# SYSTEM.net
KiCad netlist of a schematic drawn in Altium Designer
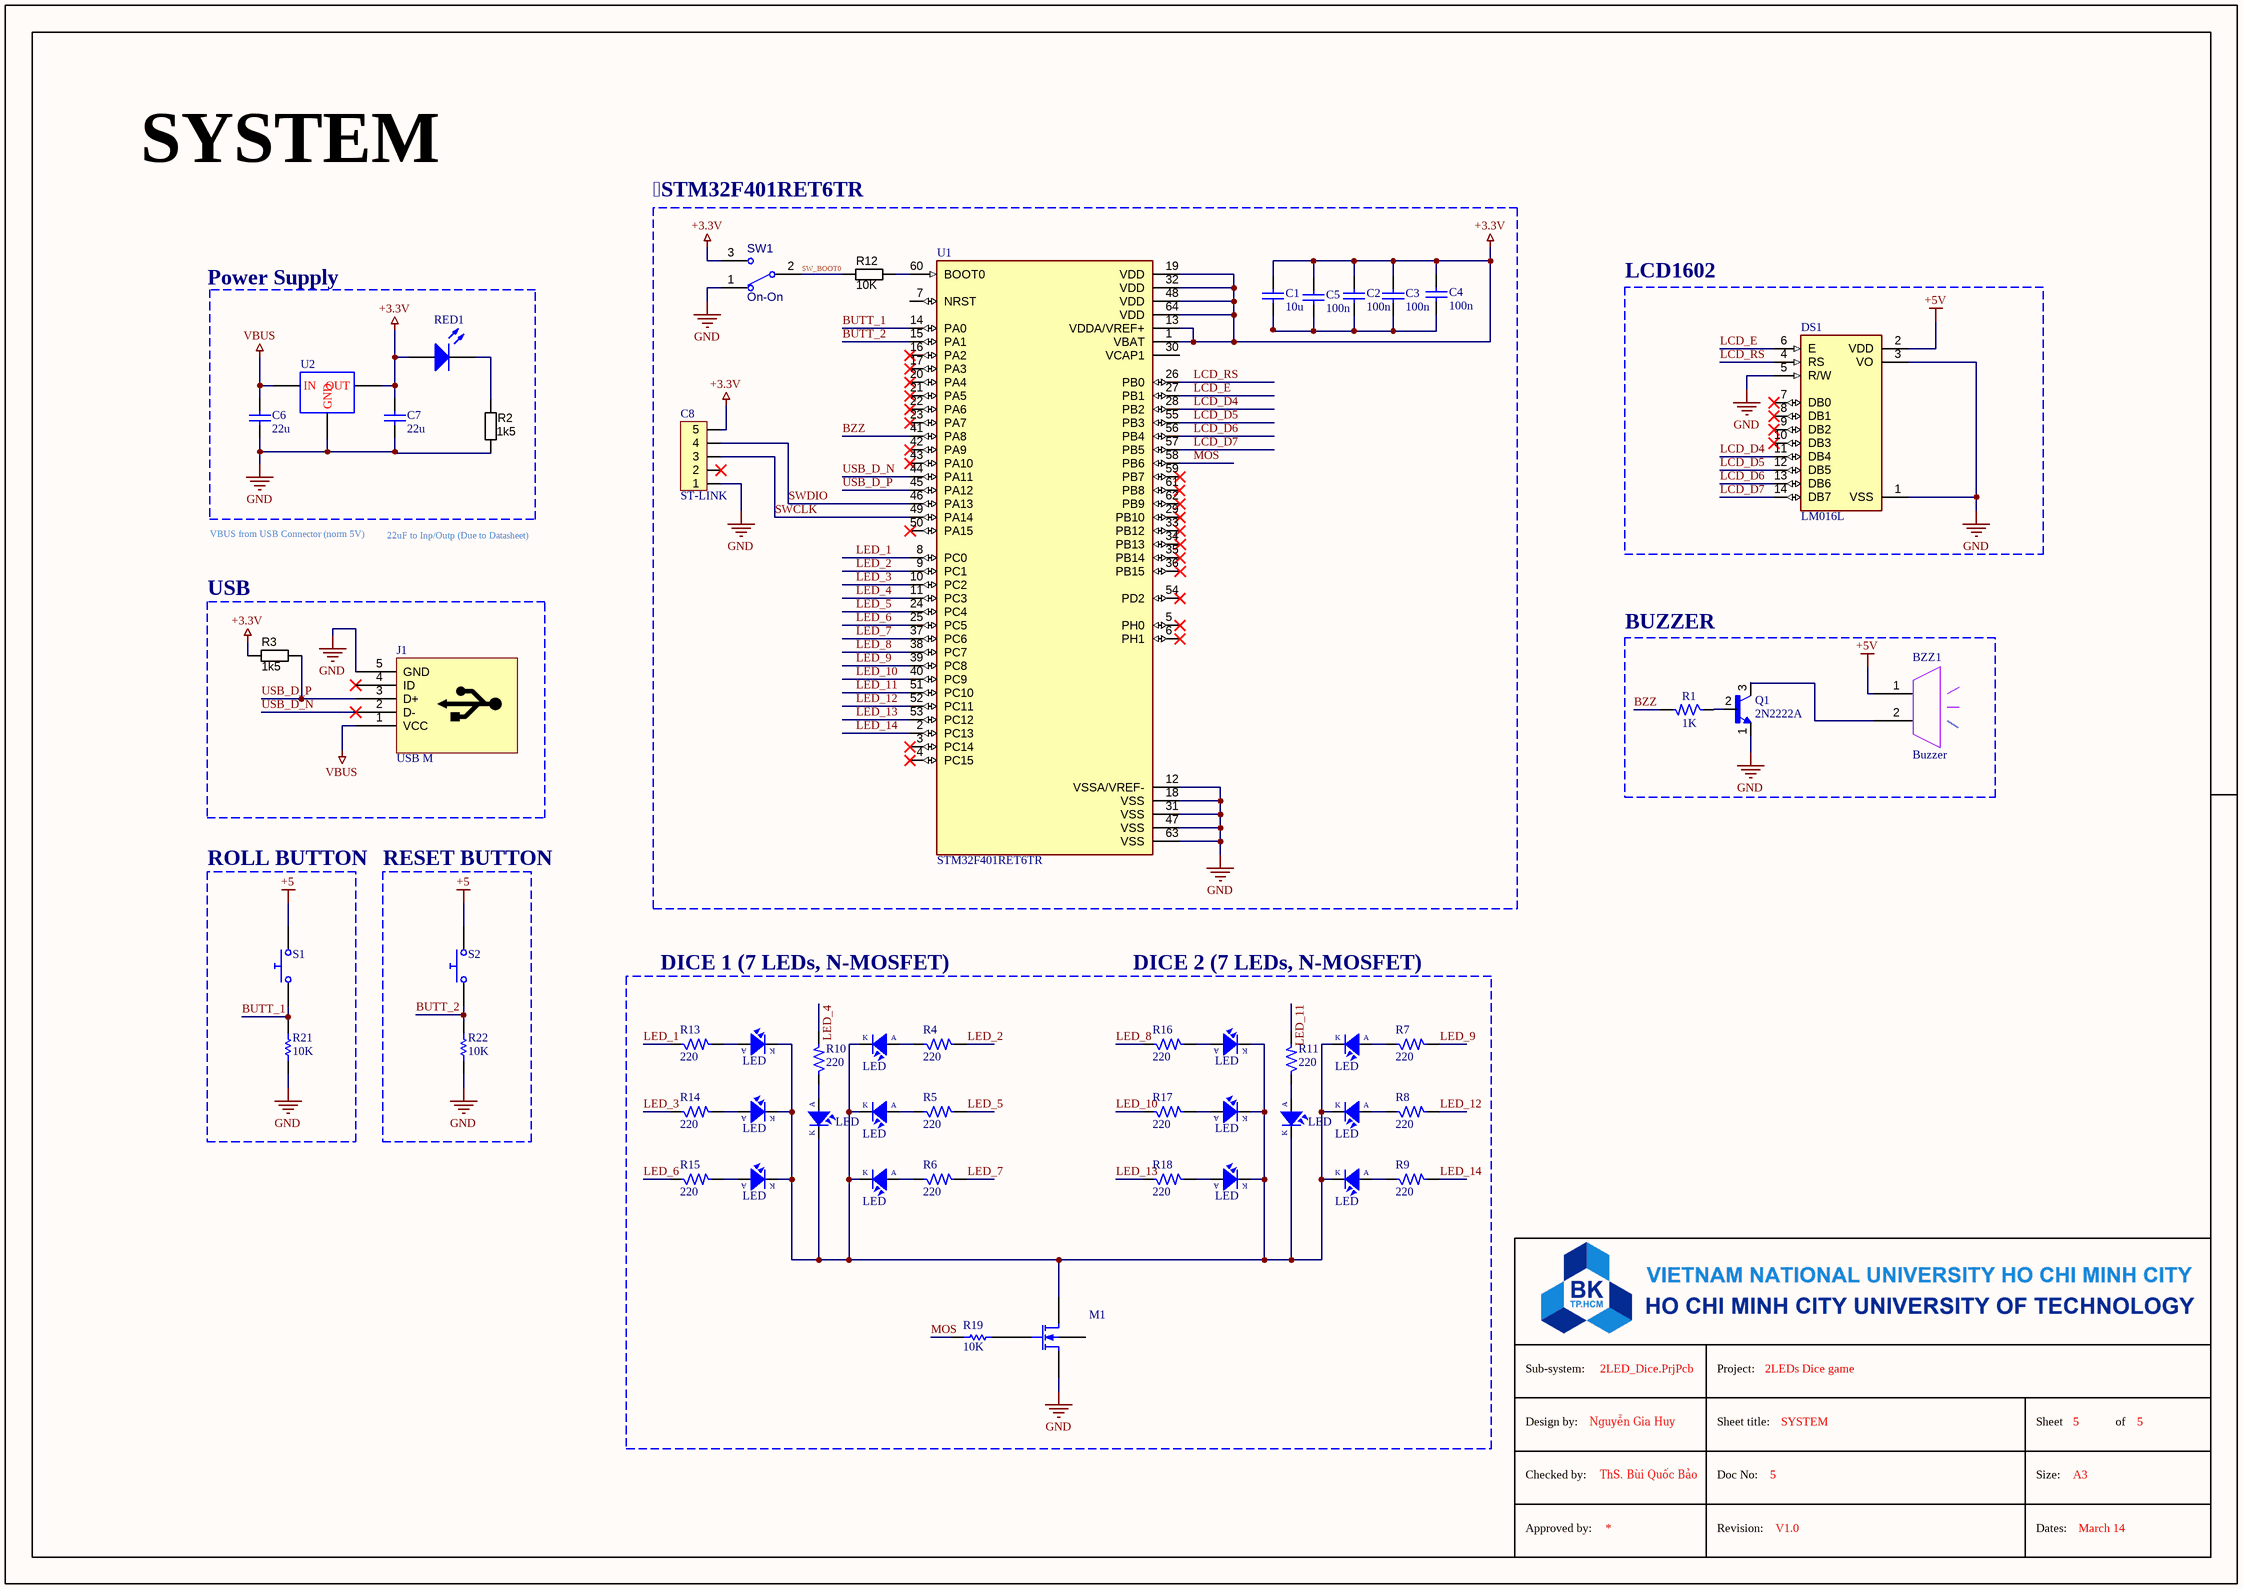
[diagram p0: SYSTEM.SchDoc]

(export (version "E")
  (design (tool "Eeschema 10.0.6"))
  (components
    (comp (ref "BZZ1")
      (value "Buzzer")
      (footprint "buzzer 5V")
      (libsource (lib "my Library") (part "Buzzer"))
    )
    (comp (ref "C1")
      (value "10u")
      (footprint "tu 0402")
      (description "Capacitor")
      (libsource (lib "Simulation Generic Components") (part "Capacitor"))
    )
    (comp (ref "C2")
      (value "100n")
      (footprint "tu 0402")
      (description "Capacitor")
      (libsource (lib "Simulation Generic Components") (part "Capacitor"))
    )
    (comp (ref "C3")
      (value "100n")
      (footprint "tu 0402")
      (description "Capacitor")
      (libsource (lib "Simulation Generic Components") (part "Capacitor"))
    )
    (comp (ref "C4")
      (value "100n")
      (footprint "tu 0402")
      (description "Capacitor")
      (libsource (lib "Simulation Generic Components") (part "Capacitor"))
    )
    (comp (ref "C5")
      (value "100n")
      (footprint "tu 0402")
      (description "Capacitor")
      (libsource (lib "Simulation Generic Components") (part "Capacitor"))
    )
    (comp (ref "C6")
      (value "22u")
      (footprint "CAPC2012X94N")
      (description "Capacitor")
      (libsource (lib "Simulation Generic Components") (part "Capacitor"))
    )
    (comp (ref "C7")
      (value "22u")
      (footprint "CAPC2012X94N")
      (description "Capacitor")
      (libsource (lib "Simulation Generic Components") (part "Capacitor"))
    )
    (comp (ref "C8")
      (value "ST-LINK")
      (footprint "HDR5")
      (description "Header IDC, 5 x 1 Pin Vertical 2.54mm Pitch (Non-Boxed, Male)")
      (fields
        (field (name "MANUFACTURER") "Würth Elektronik eiSos GmbH")
        (field (name "PARTNO") "613002143121")
        (field (name "CREATED BY") "Karrer Zheng")
      )
      (libsource (lib "LIBRARY") (part "Header5"))
    )
    (comp (ref "DS1")
      (value "LM016L")
      (footprint "MODULE_LCD-16X2")
      (description "Display Lcd 35x75mm")
      (fields (field (name "MF") "Hitachi"))
      (libsource (lib "LM016L") (part "LM016L"))
    )
    (comp (ref "J1")
      (value "USB M")
      (footprint "USB-Micr-B-FCI-SMD")
      (libsource (lib "my Library") (part "USB M"))
    )
    (comp (ref "LED1")
      (value "LED")
      (footprint "LED-3")
      (description "LED Single colour Green and Red")
      (libsource (lib "my Library") (part "LED"))
    )
    (comp (ref "LED2")
      (value "LED")
      (footprint "LED-3")
      (description "LED Single colour Green and Red")
      (libsource (lib "my Library") (part "LED"))
    )
    (comp (ref "LED3")
      (value "LED")
      (footprint "LED-3")
      (description "LED Single colour Green and Red")
      (libsource (lib "my Library") (part "LED"))
    )
    (comp (ref "LED4")
      (value "LED")
      (footprint "LED-3")
      (description "LED Single colour Green and Red")
      (libsource (lib "my Library") (part "LED"))
    )
    (comp (ref "LED5")
      (value "LED")
      (footprint "LED-3")
      (description "LED Single colour Green and Red")
      (libsource (lib "my Library") (part "LED"))
    )
    (comp (ref "LED6")
      (value "LED")
      (footprint "LED-3")
      (description "LED Single colour Green and Red")
      (libsource (lib "my Library") (part "LED"))
    )
    (comp (ref "LED7")
      (value "LED")
      (footprint "LED-3")
      (description "LED Single colour Green and Red")
      (libsource (lib "my Library") (part "LED"))
    )
    (comp (ref "LED8")
      (value "LED")
      (footprint "LED-3")
      (description "LED Single colour Green and Red")
      (libsource (lib "my Library") (part "LED"))
    )
    (comp (ref "LED9")
      (value "LED")
      (footprint "LED-3")
      (description "LED Single colour Green and Red")
      (libsource (lib "my Library") (part "LED"))
    )
    (comp (ref "LED10")
      (value "LED")
      (footprint "LED-3")
      (description "LED Single colour Green and Red")
      (libsource (lib "my Library") (part "LED"))
    )
    (comp (ref "LED11")
      (value "LED")
      (footprint "LED-3")
      (description "LED Single colour Green and Red")
      (libsource (lib "my Library") (part "LED"))
    )
    (comp (ref "LED12")
      (value "LED")
      (footprint "LED-3")
      (description "LED Single colour Green and Red")
      (libsource (lib "my Library") (part "LED"))
    )
    (comp (ref "LED13")
      (value "LED")
      (footprint "LED-3")
      (description "LED Single colour Green and Red")
      (libsource (lib "my Library") (part "LED"))
    )
    (comp (ref "LED14")
      (value "LED")
      (footprint "LED-3")
      (description "LED Single colour Green and Red")
      (libsource (lib "my Library") (part "LED"))
    )
    (comp (ref "M1")
      (value "N-channel MOS1 MOSFET Shichman and Hodges Model")
      (footprint "TO254P1054X469X1930-3")
      (libsource (lib "Simulation Generic Components") (part "MOSFET N-ch Lev1"))
    )
    (comp (ref "Q1")
      (value "2N2222A")
      (footprint "TO127P584H533-3")
      (description "Bipolar (BJT) Transistor NPN 50 V 800 mA - 500 mW Surface Mount 4-SMD")
      (fields (field (name "MF") "Microsemi Corporation"))
      (libsource (lib "2N2222A") (part "2N2222A"))
    )
    (comp (ref "R1")
      (value "1K")
      (footprint "RES-SMD-0402")
      (description "Res")
      (libsource (lib "my Library") (part "Res"))
    )
    (comp (ref "R2")
      (value "1k5")
      (footprint "RES-SMD-0402")
      (description "Resistor SMD chip 1k Ohm 0.063W 5% 0402")
      (fields (field (name "TOLERANCE") "±5%") (field (name "Comment") "Thick Film"))
      (libsource (lib "my Library") (part "RES_0402"))
    )
    (comp (ref "R3")
      (value "1k5")
      (footprint "RES-SMD-0402")
      (description "Resistor SMD chip 1k Ohm 0.063W 5% 0402")
      (fields (field (name "TOLERANCE") "±5%") (field (name "Comment") "Thick Film"))
      (libsource (lib "my Library") (part "RES_0402"))
    )
    (comp (ref "R4")
      (value "220")
      (footprint "RES-SMD-0402")
      (description "Res")
      (libsource (lib "my Library") (part "Res"))
    )
    (comp (ref "R5")
      (value "220")
      (footprint "RES-SMD-0402")
      (description "Res")
      (libsource (lib "my Library") (part "Res"))
    )
    (comp (ref "R6")
      (value "220")
      (footprint "RES-SMD-0402")
      (description "Res")
      (libsource (lib "my Library") (part "Res"))
    )
    (comp (ref "R7")
      (value "220")
      (footprint "RES-SMD-0402")
      (description "Res")
      (libsource (lib "my Library") (part "Res"))
    )
    (comp (ref "R8")
      (value "220")
      (footprint "RES-SMD-0402")
      (description "Res")
      (libsource (lib "my Library") (part "Res"))
    )
    (comp (ref "R9")
      (value "220")
      (footprint "RES-SMD-0402")
      (description "Res")
      (libsource (lib "my Library") (part "Res"))
    )
    (comp (ref "R10")
      (value "220")
      (footprint "RES-SMD-0402")
      (description "Res")
      (libsource (lib "my Library") (part "Res"))
    )
    (comp (ref "R11")
      (value "220")
      (footprint "RES-SMD-0402")
      (description "Res")
      (libsource (lib "my Library") (part "Res"))
    )
    (comp (ref "R12")
      (value "10K")
      (footprint "RES-SMD-0402")
      (description "Resistor SMD chip 1k Ohm 0.063W 5% 0402")
      (fields (field (name "TOLERANCE") "±5%") (field (name "Comment") "Thick Film"))
      (libsource (lib "") (part "RES_0402_1"))
    )
    (comp (ref "R13")
      (value "220")
      (footprint "RES-SMD-0402")
      (description "Res")
      (libsource (lib "my Library") (part "Res"))
    )
    (comp (ref "R14")
      (value "220")
      (footprint "RES-SMD-0402")
      (description "Res")
      (libsource (lib "my Library") (part "Res"))
    )
    (comp (ref "R15")
      (value "220")
      (footprint "RES-SMD-0402")
      (description "Res")
      (libsource (lib "my Library") (part "Res"))
    )
    (comp (ref "R16")
      (value "220")
      (footprint "RES-SMD-0402")
      (description "Res")
      (libsource (lib "my Library") (part "Res"))
    )
    (comp (ref "R17")
      (value "220")
      (footprint "RES-SMD-0402")
      (description "Res")
      (libsource (lib "my Library") (part "Res"))
    )
    (comp (ref "R18")
      (value "220")
      (footprint "RES-SMD-0402")
      (description "Res")
      (libsource (lib "my Library") (part "Res"))
    )
    (comp (ref "R19")
      (value "10K")
      (footprint "RES-SMD-0402")
      (description "Resistor")
      (libsource (lib "Simulation Generic Components") (part "Resistor"))
    )
    (comp (ref "R21")
      (value "10K")
      (footprint "RES-SMD-0402")
      (description "Resistor")
      (libsource (lib "Simulation Generic Components") (part "Resistor"))
    )
    (comp (ref "R22")
      (value "10K")
      (footprint "RES-SMD-0402")
      (description "Resistor")
      (libsource (lib "Simulation Generic Components") (part "Resistor"))
    )
    (comp (ref "RED1")
      (value "Light-Emitting Diode")
      (footprint "LED-RED-0805")
      (libsource (lib "Simulation Generic Components") (part "LED"))
    )
    (comp (ref "S1")
      (value "Push Button Normally Opened")
      (footprint "SW4_SMD")
      (libsource (lib "Simulation Generic Components") (part "Push Button NO"))
    )
    (comp (ref "S2")
      (value "Push Button Normally Opened")
      (footprint "SW4_SMD")
      (libsource (lib "Simulation Generic Components") (part "Push Button NO"))
    )
    (comp (ref "SW1")
      (value "ON-ON")
      (footprint "SW4_SMD")
      (description "Switch THD vertical toggle SPDT")
      (fields (field (name "SWITCH FUNCTION") "On-On"))
      (libsource (lib "my Library") (part "SW_THD_SPDT_On-On"))
    )
    (comp (ref "U1")
      (value "STM32F401RET6TR")
      (footprint "QFP50P1200X1200X160-64N")
      (fields (field (name "MF") "STMicroelectronics"))
      (libsource (lib "STM32F401RET6TR") (part "STM32F401RET6TR"))
    )
    (comp (ref "U2")
      (value "Positive Fixed Voltage regulator")
      (footprint "AMS1117_3v3")
      (libsource (lib "Simulation Generic Components") (part "Linear Voltage Regulator (Fixed)"))
    )
  )
  (nets
    (net (code "1") (name "+3.3V") (class "Default")
      (node (ref "C1") (pin "1") (pinfunction "1_1") (pintype "passive"))
      (node (ref "C2") (pin "1") (pinfunction "1_1") (pintype "passive"))
      (node (ref "C3") (pin "1") (pinfunction "1_1") (pintype "passive"))
      (node (ref "C4") (pin "1") (pinfunction "1_1") (pintype "passive"))
      (node (ref "C5") (pin "1") (pinfunction "1_1") (pintype "passive"))
      (node (ref "C7") (pin "1") (pinfunction "1_1") (pintype "passive"))
      (node (ref "C8") (pin "5") (pinfunction "5_5") (pintype "passive"))
      (node (ref "R3") (pin "1") (pinfunction "1_1") (pintype "passive"))
      (node (ref "RED1") (pin "1") (pinfunction "A_1") (pintype "passive"))
      (node (ref "SW1") (pin "3") (pinfunction "3_3") (pintype "passive"))
      (node (ref "U1") (pin "1") (pinfunction "VBAT_1") (pintype "power_in"))
      (node (ref "U1") (pin "13") (pinfunction "VDDA/VREF+_13") (pintype "power_in"))
      (node (ref "U1") (pin "19") (pinfunction "VDD_19") (pintype "power_in"))
      (node (ref "U1") (pin "32") (pinfunction "VDD_32") (pintype "power_in"))
      (node (ref "U1") (pin "48") (pinfunction "VDD_48") (pintype "power_in"))
      (node (ref "U1") (pin "64") (pinfunction "VDD_64") (pintype "power_in"))
      (node (ref "U2") (pin "3") (pinfunction "OUT_3") (pintype "passive"))
    )
    (net (code "2") (name "+5") (class "Default")
      (node (ref "S1") (pin "2") (pinfunction "2_2") (pintype "passive"))
      (node (ref "S2") (pin "2") (pinfunction "2_2") (pintype "passive"))
    )
    (net (code "3") (name "+5V") (class "Default")
      (node (ref "BZZ1") (pin "1") (pinfunction "1_1") (pintype "passive"))
      (node (ref "DS1") (pin "2") (pinfunction "VDD_2") (pintype "power_in"))
    )
    (net (code "4") (name "/BUTT_1") (class "Default")
      (node (ref "R21") (pin "2") (pinfunction "2_2") (pintype "passive"))
      (node (ref "S1") (pin "1") (pinfunction "1_1") (pintype "passive"))
      (node (ref "U1") (pin "14") (pinfunction "PA0_14") (pintype "bidirectional"))
    )
    (net (code "5") (name "/BUTT_2") (class "Default")
      (node (ref "R22") (pin "2") (pinfunction "2_2") (pintype "passive"))
      (node (ref "S2") (pin "1") (pinfunction "1_1") (pintype "passive"))
      (node (ref "U1") (pin "15") (pinfunction "PA1_15") (pintype "bidirectional"))
    )
    (net (code "6") (name "/BZZ") (class "Default")
      (node (ref "R1") (pin "2") (pinfunction "2_2") (pintype "passive"))
      (node (ref "U1") (pin "41") (pinfunction "PA8_41") (pintype "bidirectional"))
    )
    (net (code "7") (name "/LCD_D4") (class "Default")
      (node (ref "DS1") (pin "11") (pinfunction "DB4_11") (pintype "bidirectional"))
      (node (ref "U1") (pin "28") (pinfunction "PB2_28") (pintype "bidirectional"))
    )
    (net (code "8") (name "/LCD_D5") (class "Default")
      (node (ref "DS1") (pin "12") (pinfunction "DB5_12") (pintype "bidirectional"))
      (node (ref "U1") (pin "55") (pinfunction "PB3_55") (pintype "bidirectional"))
    )
    (net (code "9") (name "/LCD_D6") (class "Default")
      (node (ref "DS1") (pin "13") (pinfunction "DB6_13") (pintype "bidirectional"))
      (node (ref "U1") (pin "56") (pinfunction "PB4_56") (pintype "bidirectional"))
    )
    (net (code "10") (name "/LCD_D7") (class "Default")
      (node (ref "DS1") (pin "14") (pinfunction "DB7_14") (pintype "bidirectional"))
      (node (ref "U1") (pin "57") (pinfunction "PB5_57") (pintype "bidirectional"))
    )
    (net (code "11") (name "/LCD_E") (class "Default")
      (node (ref "DS1") (pin "6") (pinfunction "E_6") (pintype "input"))
      (node (ref "U1") (pin "27") (pinfunction "PB1_27") (pintype "bidirectional"))
    )
    (net (code "12") (name "/LCD_RS") (class "Default")
      (node (ref "DS1") (pin "4") (pinfunction "RS_4") (pintype "input"))
      (node (ref "U1") (pin "26") (pinfunction "PB0_26") (pintype "bidirectional"))
    )
    (net (code "13") (name "/LED_1") (class "Default")
      (node (ref "R13") (pin "1") (pinfunction "1_1") (pintype "passive"))
      (node (ref "U1") (pin "8") (pinfunction "PC0_8") (pintype "bidirectional"))
    )
    (net (code "14") (name "/LED_2") (class "Default")
      (node (ref "R4") (pin "2") (pinfunction "2_2") (pintype "passive"))
      (node (ref "U1") (pin "9") (pinfunction "PC1_9") (pintype "bidirectional"))
    )
    (net (code "15") (name "/LED_3") (class "Default")
      (node (ref "R14") (pin "1") (pinfunction "1_1") (pintype "passive"))
      (node (ref "U1") (pin "10") (pinfunction "PC2_10") (pintype "bidirectional"))
    )
    (net (code "16") (name "/LED_4") (class "Default")
      (node (ref "R10") (pin "2") (pinfunction "2_2") (pintype "passive"))
      (node (ref "U1") (pin "11") (pinfunction "PC3_11") (pintype "bidirectional"))
    )
    (net (code "17") (name "/LED_5") (class "Default")
      (node (ref "R5") (pin "2") (pinfunction "2_2") (pintype "passive"))
      (node (ref "U1") (pin "24") (pinfunction "PC4_24") (pintype "bidirectional"))
    )
    (net (code "18") (name "/LED_6") (class "Default")
      (node (ref "R15") (pin "1") (pinfunction "1_1") (pintype "passive"))
      (node (ref "U1") (pin "25") (pinfunction "PC5_25") (pintype "bidirectional"))
    )
    (net (code "19") (name "/LED_7") (class "Default")
      (node (ref "R6") (pin "2") (pinfunction "2_2") (pintype "passive"))
      (node (ref "U1") (pin "37") (pinfunction "PC6_37") (pintype "bidirectional"))
    )
    (net (code "20") (name "/LED_8") (class "Default")
      (node (ref "R16") (pin "1") (pinfunction "1_1") (pintype "passive"))
      (node (ref "U1") (pin "38") (pinfunction "PC7_38") (pintype "bidirectional"))
    )
    (net (code "21") (name "/LED_9") (class "Default")
      (node (ref "R7") (pin "2") (pinfunction "2_2") (pintype "passive"))
      (node (ref "U1") (pin "39") (pinfunction "PC8_39") (pintype "bidirectional"))
    )
    (net (code "22") (name "/LED_10") (class "Default")
      (node (ref "R17") (pin "1") (pinfunction "1_1") (pintype "passive"))
      (node (ref "U1") (pin "40") (pinfunction "PC9_40") (pintype "bidirectional"))
    )
    (net (code "23") (name "/LED_11") (class "Default")
      (node (ref "R11") (pin "2") (pinfunction "2_2") (pintype "passive"))
      (node (ref "U1") (pin "51") (pinfunction "PC10_51") (pintype "bidirectional"))
    )
    (net (code "24") (name "/LED_12") (class "Default")
      (node (ref "R8") (pin "2") (pinfunction "2_2") (pintype "passive"))
      (node (ref "U1") (pin "52") (pinfunction "PC11_52") (pintype "bidirectional"))
    )
    (net (code "25") (name "/LED_13") (class "Default")
      (node (ref "R18") (pin "1") (pinfunction "1_1") (pintype "passive"))
      (node (ref "U1") (pin "53") (pinfunction "PC12_53") (pintype "bidirectional"))
    )
    (net (code "26") (name "/LED_14") (class "Default")
      (node (ref "R9") (pin "2") (pinfunction "2_2") (pintype "passive"))
      (node (ref "U1") (pin "2") (pinfunction "PC13_2") (pintype "bidirectional"))
    )
    (net (code "27") (name "/MOS") (class "Default")
      (node (ref "R19") (pin "2") (pinfunction "2_2") (pintype "passive"))
      (node (ref "U1") (pin "58") (pinfunction "PB6_58") (pintype "bidirectional"))
    )
    (net (code "28") (name "/SWCLK") (class "Default")
      (node (ref "C8") (pin "3") (pinfunction "3_3") (pintype "passive"))
      (node (ref "U1") (pin "49") (pinfunction "PA14_49") (pintype "bidirectional"))
    )
    (net (code "29") (name "/SWDIO") (class "Default")
      (node (ref "C8") (pin "4") (pinfunction "4_4") (pintype "passive"))
      (node (ref "U1") (pin "46") (pinfunction "PA13_46") (pintype "bidirectional"))
    )
    (net (code "30") (name "/SW_BOOT0") (class "Default")
      (node (ref "R12") (pin "2") (pinfunction "2_2") (pintype "passive"))
      (node (ref "SW1") (pin "2") (pinfunction "2_2") (pintype "passive"))
    )
    (net (code "31") (name "/USB_D_N") (class "Default")
      (node (ref "J1") (pin "2") (pinfunction "D-_2") (pintype "passive"))
      (node (ref "U1") (pin "44") (pinfunction "PA11_44") (pintype "bidirectional"))
    )
    (net (code "32") (name "/USB_D_P") (class "Default")
      (node (ref "J1") (pin "3") (pinfunction "D+_3") (pintype "passive"))
      (node (ref "R3") (pin "2") (pinfunction "2_2") (pintype "passive"))
      (node (ref "U1") (pin "45") (pinfunction "PA12_45") (pintype "bidirectional"))
    )
    (net (code "33") (name "GND") (class "Default")
      (node (ref "C6") (pin "2") (pinfunction "2_2") (pintype "passive"))
      (node (ref "C7") (pin "2") (pinfunction "2_2") (pintype "passive"))
      (node (ref "C8") (pin "1") (pinfunction "1_1") (pintype "passive"))
      (node (ref "DS1") (pin "1") (pinfunction "VSS_1") (pintype "power_in"))
      (node (ref "DS1") (pin "3") (pinfunction "VO_3") (pintype "power_in"))
      (node (ref "DS1") (pin "5") (pinfunction "R/W_5") (pintype "input"))
      (node (ref "J1") (pin "5") (pinfunction "GND_5") (pintype "passive"))
      (node (ref "M1") (pin "3") (pinfunction "S_3") (pintype "passive"))
      (node (ref "Q1") (pin "1") (pinfunction "E_1") (pintype "passive"))
      (node (ref "R2") (pin "1") (pinfunction "1_1") (pintype "passive"))
      (node (ref "R21") (pin "1") (pinfunction "1_1") (pintype "passive"))
      (node (ref "R22") (pin "1") (pinfunction "1_1") (pintype "passive"))
      (node (ref "SW1") (pin "1") (pinfunction "1_1") (pintype "passive"))
      (node (ref "U1") (pin "12") (pinfunction "VSSA/VREF-_12") (pintype "power_in"))
      (node (ref "U1") (pin "18") (pinfunction "VSS_18") (pintype "power_in"))
      (node (ref "U1") (pin "31") (pinfunction "VSS_31") (pintype "power_in"))
      (node (ref "U1") (pin "47") (pinfunction "VSS_47") (pintype "power_in"))
      (node (ref "U1") (pin "63") (pinfunction "VSS_63") (pintype "power_in"))
      (node (ref "U2") (pin "2") (pinfunction "GND_2") (pintype "passive"))
    )
    (net (code "34") (name "Net-(C1-Pad2)") (class "Default")
      (node (ref "C1") (pin "2") (pinfunction "2_2") (pintype "passive"))
      (node (ref "C2") (pin "2") (pinfunction "2_2") (pintype "passive"))
      (node (ref "C3") (pin "2") (pinfunction "2_2") (pintype "passive"))
      (node (ref "C4") (pin "2") (pinfunction "2_2") (pintype "passive"))
      (node (ref "C5") (pin "2") (pinfunction "2_2") (pintype "passive"))
    )
    (net (code "35") (name "Net-(LED1-A)") (class "Default")
      (node (ref "LED1") (pin "1") (pinfunction "A_1") (pintype "passive"))
      (node (ref "R4") (pin "1") (pinfunction "1_1") (pintype "passive"))
    )
    (net (code "36") (name "Net-(LED1-K)") (class "Default")
      (node (ref "LED1") (pin "2") (pinfunction "K_2") (pintype "passive"))
      (node (ref "LED10") (pin "2") (pinfunction "K_2") (pintype "passive"))
      (node (ref "LED11") (pin "2") (pinfunction "K_2") (pintype "passive"))
      (node (ref "LED12") (pin "2") (pinfunction "K_2") (pintype "passive"))
      (node (ref "LED13") (pin "2") (pinfunction "K_2") (pintype "passive"))
      (node (ref "LED14") (pin "2") (pinfunction "K_2") (pintype "passive"))
      (node (ref "LED2") (pin "2") (pinfunction "K_2") (pintype "passive"))
      (node (ref "LED3") (pin "2") (pinfunction "K_2") (pintype "passive"))
      (node (ref "LED4") (pin "2") (pinfunction "K_2") (pintype "passive"))
      (node (ref "LED5") (pin "2") (pinfunction "K_2") (pintype "passive"))
      (node (ref "LED6") (pin "2") (pinfunction "K_2") (pintype "passive"))
      (node (ref "LED7") (pin "2") (pinfunction "K_2") (pintype "passive"))
      (node (ref "LED8") (pin "2") (pinfunction "K_2") (pintype "passive"))
      (node (ref "LED9") (pin "2") (pinfunction "K_2") (pintype "passive"))
      (node (ref "M1") (pin "1") (pinfunction "D_1") (pintype "passive"))
    )
    (net (code "37") (name "Net-(LED2-A)") (class "Default")
      (node (ref "LED2") (pin "1") (pinfunction "A_1") (pintype "passive"))
      (node (ref "R5") (pin "1") (pinfunction "1_1") (pintype "passive"))
    )
    (net (code "38") (name "Net-(LED3-A)") (class "Default")
      (node (ref "LED3") (pin "1") (pinfunction "A_1") (pintype "passive"))
      (node (ref "R6") (pin "1") (pinfunction "1_1") (pintype "passive"))
    )
    (net (code "39") (name "Net-(LED4-A)") (class "Default")
      (node (ref "LED4") (pin "1") (pinfunction "A_1") (pintype "passive"))
      (node (ref "R7") (pin "1") (pinfunction "1_1") (pintype "passive"))
    )
    (net (code "40") (name "Net-(LED5-A)") (class "Default")
      (node (ref "LED5") (pin "1") (pinfunction "A_1") (pintype "passive"))
      (node (ref "R8") (pin "1") (pinfunction "1_1") (pintype "passive"))
    )
    (net (code "41") (name "Net-(LED6-A)") (class "Default")
      (node (ref "LED6") (pin "1") (pinfunction "A_1") (pintype "passive"))
      (node (ref "R9") (pin "1") (pinfunction "1_1") (pintype "passive"))
    )
    (net (code "42") (name "Net-(LED7-A)") (class "Default")
      (node (ref "LED7") (pin "1") (pinfunction "A_1") (pintype "passive"))
      (node (ref "R10") (pin "1") (pinfunction "1_1") (pintype "passive"))
    )
    (net (code "43") (name "Net-(LED8-A)") (class "Default")
      (node (ref "LED8") (pin "1") (pinfunction "A_1") (pintype "passive"))
      (node (ref "R11") (pin "1") (pinfunction "1_1") (pintype "passive"))
    )
    (net (code "44") (name "Net-(LED9-A)") (class "Default")
      (node (ref "LED9") (pin "1") (pinfunction "A_1") (pintype "passive"))
      (node (ref "R13") (pin "2") (pinfunction "2_2") (pintype "passive"))
    )
    (net (code "45") (name "Net-(LED10-A)") (class "Default")
      (node (ref "LED10") (pin "1") (pinfunction "A_1") (pintype "passive"))
      (node (ref "R14") (pin "2") (pinfunction "2_2") (pintype "passive"))
    )
    (net (code "46") (name "Net-(LED11-A)") (class "Default")
      (node (ref "LED11") (pin "1") (pinfunction "A_1") (pintype "passive"))
      (node (ref "R15") (pin "2") (pinfunction "2_2") (pintype "passive"))
    )
    (net (code "47") (name "Net-(LED12-A)") (class "Default")
      (node (ref "LED12") (pin "1") (pinfunction "A_1") (pintype "passive"))
      (node (ref "R16") (pin "2") (pinfunction "2_2") (pintype "passive"))
    )
    (net (code "48") (name "Net-(LED13-A)") (class "Default")
      (node (ref "LED13") (pin "1") (pinfunction "A_1") (pintype "passive"))
      (node (ref "R17") (pin "2") (pinfunction "2_2") (pintype "passive"))
    )
    (net (code "49") (name "Net-(LED14-A)") (class "Default")
      (node (ref "LED14") (pin "1") (pinfunction "A_1") (pintype "passive"))
      (node (ref "R18") (pin "2") (pinfunction "2_2") (pintype "passive"))
    )
    (net (code "50") (name "Net-(M1-G)") (class "Default")
      (node (ref "M1") (pin "2") (pinfunction "G_2") (pintype "passive"))
      (node (ref "R19") (pin "1") (pinfunction "1_1") (pintype "passive"))
    )
    (net (code "51") (name "Net-(Q1-B)") (class "Default")
      (node (ref "Q1") (pin "2") (pinfunction "B_2") (pintype "passive"))
      (node (ref "R1") (pin "1") (pinfunction "1_1") (pintype "passive"))
    )
    (net (code "52") (name "Net-(Q1-C)") (class "Default")
      (node (ref "BZZ1") (pin "2") (pinfunction "2_2") (pintype "passive"))
      (node (ref "Q1") (pin "3") (pinfunction "C_3") (pintype "passive"))
    )
    (net (code "53") (name "Net-(RED1-K)") (class "Default")
      (node (ref "R2") (pin "2") (pinfunction "2_2") (pintype "passive"))
      (node (ref "RED1") (pin "2") (pinfunction "K_2") (pintype "passive"))
    )
    (net (code "54") (name "Net-(U1-BOOT0)") (class "Default")
      (node (ref "R12") (pin "1") (pinfunction "1_1") (pintype "passive"))
      (node (ref "U1") (pin "60") (pinfunction "BOOT0_60") (pintype "input"))
    )
    (net (code "55") (name "VBUS") (class "Default")
      (node (ref "C6") (pin "1") (pinfunction "1_1") (pintype "passive"))
      (node (ref "J1") (pin "1") (pinfunction "VCC_1") (pintype "passive"))
      (node (ref "U2") (pin "1") (pinfunction "IN_1") (pintype "passive"))
    )
    (net (code "56") (name "unconnected-(C8-Pad2)") (class "Default")
      (node (ref "C8") (pin "2") (pinfunction "2_2") (pintype "passive+no_connect"))
    )
    (net (code "57") (name "unconnected-(DS1-DB0-Pad7)") (class "Default")
      (node (ref "DS1") (pin "7") (pinfunction "DB0_7") (pintype "bidirectional+no_connect"))
    )
    (net (code "58") (name "unconnected-(DS1-DB1-Pad8)") (class "Default")
      (node (ref "DS1") (pin "8") (pinfunction "DB1_8") (pintype "bidirectional+no_connect"))
    )
    (net (code "59") (name "unconnected-(DS1-DB2-Pad9)") (class "Default")
      (node (ref "DS1") (pin "9") (pinfunction "DB2_9") (pintype "bidirectional+no_connect"))
    )
    (net (code "60") (name "unconnected-(DS1-DB3-Pad10)") (class "Default")
      (node (ref "DS1") (pin "10") (pinfunction "DB3_10") (pintype "bidirectional+no_connect"))
    )
    (net (code "61") (name "unconnected-(J1-ID-Pad4)") (class "Default")
      (node (ref "J1") (pin "4") (pinfunction "ID_4") (pintype "passive+no_connect"))
    )
    (net (code "62") (name "unconnected-(M1-B-Pad4)") (class "Default")
      (node (ref "M1") (pin "4") (pinfunction "B_4") (pintype "passive"))
    )
    (net (code "63") (name "unconnected-(U1-NRST-Pad7)") (class "Default")
      (node (ref "U1") (pin "7") (pinfunction "NRST_7") (pintype "bidirectional"))
    )
    (net (code "64") (name "unconnected-(U1-PA2-Pad16)") (class "Default")
      (node (ref "U1") (pin "16") (pinfunction "PA2_16") (pintype "bidirectional+no_connect"))
    )
    (net (code "65") (name "unconnected-(U1-PA3-Pad17)") (class "Default")
      (node (ref "U1") (pin "17") (pinfunction "PA3_17") (pintype "bidirectional+no_connect"))
    )
    (net (code "66") (name "unconnected-(U1-PA4-Pad20)") (class "Default")
      (node (ref "U1") (pin "20") (pinfunction "PA4_20") (pintype "bidirectional+no_connect"))
    )
    (net (code "67") (name "unconnected-(U1-PA5-Pad21)") (class "Default")
      (node (ref "U1") (pin "21") (pinfunction "PA5_21") (pintype "bidirectional+no_connect"))
    )
    (net (code "68") (name "unconnected-(U1-PA6-Pad22)") (class "Default")
      (node (ref "U1") (pin "22") (pinfunction "PA6_22") (pintype "bidirectional+no_connect"))
    )
    (net (code "69") (name "unconnected-(U1-PA7-Pad23)") (class "Default")
      (node (ref "U1") (pin "23") (pinfunction "PA7_23") (pintype "bidirectional+no_connect"))
    )
    (net (code "70") (name "unconnected-(U1-PA9-Pad42)") (class "Default")
      (node (ref "U1") (pin "42") (pinfunction "PA9_42") (pintype "bidirectional+no_connect"))
    )
    (net (code "71") (name "unconnected-(U1-PA10-Pad43)") (class "Default")
      (node (ref "U1") (pin "43") (pinfunction "PA10_43") (pintype "bidirectional+no_connect"))
    )
    (net (code "72") (name "unconnected-(U1-PA15-Pad50)") (class "Default")
      (node (ref "U1") (pin "50") (pinfunction "PA15_50") (pintype "bidirectional"))
    )
    (net (code "73") (name "unconnected-(U1-PB7-Pad59)") (class "Default")
      (node (ref "U1") (pin "59") (pinfunction "PB7_59") (pintype "bidirectional+no_connect"))
    )
    (net (code "74") (name "unconnected-(U1-PB8-Pad61)") (class "Default")
      (node (ref "U1") (pin "61") (pinfunction "PB8_61") (pintype "bidirectional"))
    )
    (net (code "75") (name "unconnected-(U1-PB9-Pad62)") (class "Default")
      (node (ref "U1") (pin "62") (pinfunction "PB9_62") (pintype "bidirectional+no_connect"))
    )
    (net (code "76") (name "unconnected-(U1-PB10-Pad29)") (class "Default")
      (node (ref "U1") (pin "29") (pinfunction "PB10_29") (pintype "bidirectional+no_connect"))
    )
    (net (code "77") (name "unconnected-(U1-PB12-Pad33)") (class "Default")
      (node (ref "U1") (pin "33") (pinfunction "PB12_33") (pintype "bidirectional+no_connect"))
    )
    (net (code "78") (name "unconnected-(U1-PB13-Pad34)") (class "Default")
      (node (ref "U1") (pin "34") (pinfunction "PB13_34") (pintype "bidirectional"))
    )
    (net (code "79") (name "unconnected-(U1-PB14-Pad35)") (class "Default")
      (node (ref "U1") (pin "35") (pinfunction "PB14_35") (pintype "bidirectional+no_connect"))
    )
    (net (code "80") (name "unconnected-(U1-PB15-Pad36)") (class "Default")
      (node (ref "U1") (pin "36") (pinfunction "PB15_36") (pintype "bidirectional"))
    )
    (net (code "81") (name "unconnected-(U1-PC14-Pad3)") (class "Default")
      (node (ref "U1") (pin "3") (pinfunction "PC14_3") (pintype "bidirectional+no_connect"))
    )
    (net (code "82") (name "unconnected-(U1-PC15-Pad4)") (class "Default")
      (node (ref "U1") (pin "4") (pinfunction "PC15_4") (pintype "bidirectional+no_connect"))
    )
    (net (code "83") (name "unconnected-(U1-PD2-Pad54)") (class "Default")
      (node (ref "U1") (pin "54") (pinfunction "PD2_54") (pintype "bidirectional+no_connect"))
    )
    (net (code "84") (name "unconnected-(U1-PH0-Pad5)") (class "Default")
      (node (ref "U1") (pin "5") (pinfunction "PH0_5") (pintype "bidirectional+no_connect"))
    )
    (net (code "85") (name "unconnected-(U1-PH1-Pad6)") (class "Default")
      (node (ref "U1") (pin "6") (pinfunction "PH1_6") (pintype "bidirectional+no_connect"))
    )
    (net (code "86") (name "unconnected-(U1-VCAP1-Pad30)") (class "Default")
      (node (ref "U1") (pin "30") (pinfunction "VCAP1_30") (pintype "power_in"))
    )
  )
)
